# Schematico_Pompa.net
KiCad netlist of a schematic drawn in Altium Designer
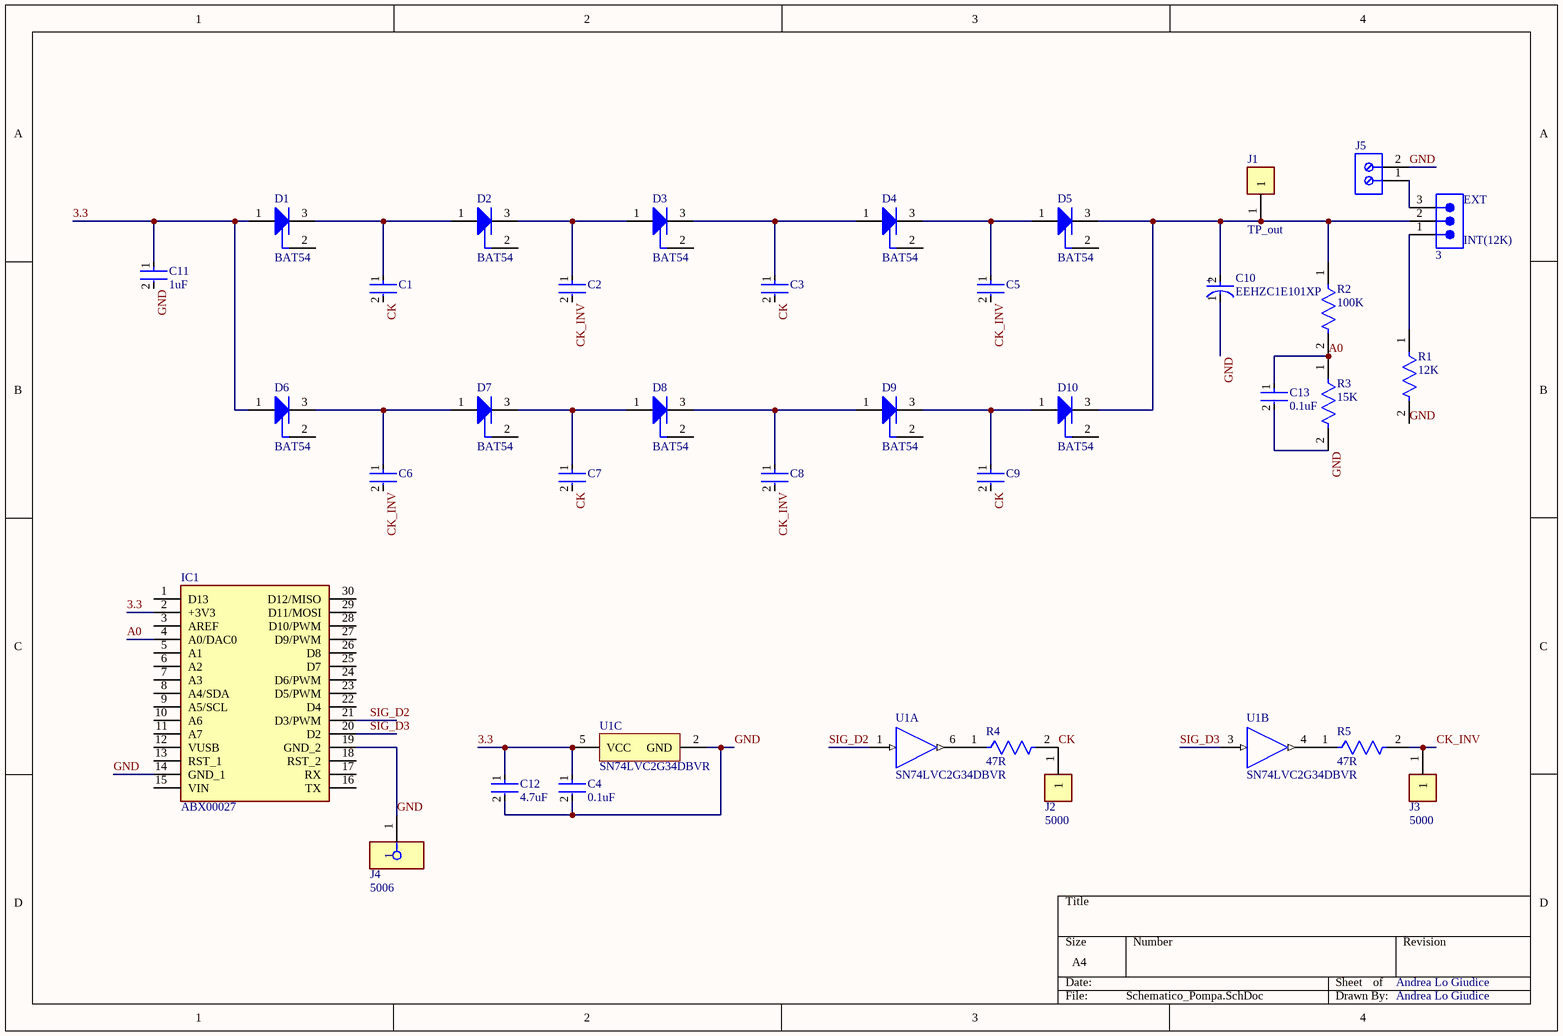
[diagram p0: Schematico_Pompa.SchDoc]

(export (version "E")
  (design (tool "Eeschema 10.0.6"))
  (components
    (comp (ref "3")
      (value "TSW-103-07-T-S")
      (footprint "SMTC-TSW-103-07-X-S")
      (description "0.025\" SQ Post Header, Through-hole, Vertical, -55 to 105 degC, 2.54 mm Pitch, 3-Pin, Male, RoHS")
      (fields (field (name "MANUFACTURER") "Samtec"))
      (libsource (lib "Altium Content Vault") (part "SMTC-TSW-103-X-X-S-X"))
    )
    (comp (ref "C1")
      (value "GRM188Z71E225ME43D")
      (footprint "FP-GRM188-0_2-IPC_C")
      (description "Chip Multilayer Ceramic Capacitors for General Purpose, 0603, 2.2uF, X7R, 15%, 20%, 25V")
      (libsource (lib "Altium Content Vault") (part "11868f565c42a9108669ba33697ecf6"))
    )
    (comp (ref "C2")
      (value "GRM188Z71E225ME43D")
      (footprint "FP-GRM188-0_2-IPC_C")
      (description "Chip Multilayer Ceramic Capacitors for General Purpose, 0603, 2.2uF, X7R, 15%, 20%, 25V")
      (libsource (lib "Altium Content Vault") (part "11868f565c42a9108669ba33697ecf6"))
    )
    (comp (ref "C3")
      (value "GRM188Z71E225ME43D")
      (footprint "FP-GRM188-0_2-IPC_C")
      (description "Chip Multilayer Ceramic Capacitors for General Purpose, 0603, 2.2uF, X7R, 15%, 20%, 25V")
      (libsource (lib "Altium Content Vault") (part "11868f565c42a9108669ba33697ecf6"))
    )
    (comp (ref "C4")
      (value "0.1uF")
      (footprint "FP-C0603C-CF-IPC_B")
      (description "CAP CER 0.1UF 16V X7R 0603")
      (fields (field (name "MANUFACTURER PART NUMBER") "C0603C104M4RACTU") (field (name "TOLERANCE") "0.2"))
      (libsource (lib "Altium Content Vault") (part "b4654b650e69147ec39a6b967a45e02"))
    )
    (comp (ref "C5")
      (value "GRM188Z71E225ME43D")
      (footprint "FP-GRM188-0_2-IPC_C")
      (description "Chip Multilayer Ceramic Capacitors for General Purpose, 0603, 2.2uF, X7R, 15%, 20%, 25V")
      (libsource (lib "Altium Content Vault") (part "11868f565c42a9108669ba33697ecf6"))
    )
    (comp (ref "C6")
      (value "GRM188Z71E225ME43D")
      (footprint "FP-GRM188-0_2-IPC_C")
      (description "Chip Multilayer Ceramic Capacitors for General Purpose, 0603, 2.2uF, X7R, 15%, 20%, 25V")
      (libsource (lib "Altium Content Vault") (part "11868f565c42a9108669ba33697ecf6"))
    )
    (comp (ref "C7")
      (value "GRM188Z71E225ME43D")
      (footprint "FP-GRM188-0_2-IPC_C")
      (description "Chip Multilayer Ceramic Capacitors for General Purpose, 0603, 2.2uF, X7R, 15%, 20%, 25V")
      (libsource (lib "Altium Content Vault") (part "11868f565c42a9108669ba33697ecf6"))
    )
    (comp (ref "C8")
      (value "GRM188Z71E225ME43D")
      (footprint "FP-GRM188-0_2-IPC_C")
      (description "Chip Multilayer Ceramic Capacitors for General Purpose, 0603, 2.2uF, X7R, 15%, 20%, 25V")
      (libsource (lib "Altium Content Vault") (part "11868f565c42a9108669ba33697ecf6"))
    )
    (comp (ref "C9")
      (value "GRM188Z71E225ME43D")
      (footprint "FP-GRM188-0_2-IPC_C")
      (description "Chip Multilayer Ceramic Capacitors for General Purpose, 0603, 2.2uF, X7R, 15%, 20%, 25V")
      (libsource (lib "Altium Content Vault") (part "11868f565c42a9108669ba33697ecf6"))
    )
    (comp (ref "C10")
      (value "EEHZC1E101XP")
      (footprint "FP-EEH-D8-MFG")
      (description "Conductive Polymer Hybrid Aluminum Electrolytic Capacitors 100uF ±20% 25V RADIAL SMT 6.3x7.7mm")
      (fields (field (name "TOLERANCE") "20%") (field (name "VOLTAGE") "25V"))
      (libsource (lib "Altium Content Vault") (part "a00bbbee19879c290e62620ae7e47b1"))
    )
    (comp (ref "C11")
      (value "1uF")
      (footprint "FP-CC0603-DA-IPC_B")
      (description "CC0603 1 uF X7R 10.00% 25 V")
      (fields
        (field (name "OCTOPART") "https://octopart.com/cc0603kpx7r8bb105-yageo-95714672")
        (field (name "MANUFACTURER PART NUMBER") "CC0603KPX7R8BB105")
      )
      (libsource (lib "Altium Content Vault") (part "11868f565c42a9108669ba33697ecf6"))
    )
    (comp (ref "C12")
      (value "4.7uF")
      (footprint "FP-CC0603-DA-IPC_B")
      (description "CAP CER 4.7UF 25V X5R 0603")
      (fields
        (field (name "OCTOPART") "https://octopart.com/cc0603mrx5r8bb475-yageo-81932637")
        (field (name "VOLTAGE") "25 V")
      )
      (libsource (lib "Altium Content Vault") (part "11868f565c42a9108669ba33697ecf6"))
    )
    (comp (ref "C13")
      (value "0.1uF")
      (footprint "FP-C0603C-CF-IPC_B")
      (description "CAP CER 0.1UF 16V X7R 0603")
      (fields (field (name "MANUFACTURER PART NUMBER") "C0603C104M4RACTU") (field (name "TOLERANCE") "0.2"))
      (libsource (lib "Altium Content Vault") (part "b4654b650e69147ec39a6b967a45e02"))
    )
    (comp (ref "D1")
      (value "BAT54")
      (footprint "INF-SOT23_L")
      (description "Silicon Schottky Diode, SOT23, Reel, Green")
      (fields (field (name "MANUFACTURER") "Infineon"))
      (libsource (lib "Altium Content Vault") (part "INF-D_A1K3-3"))
    )
    (comp (ref "D2")
      (value "BAT54")
      (footprint "INF-SOT23_L")
      (description "Silicon Schottky Diode, SOT23, Reel, Green")
      (fields (field (name "MANUFACTURER") "Infineon"))
      (libsource (lib "Altium Content Vault") (part "INF-D_A1K3-3"))
    )
    (comp (ref "D3")
      (value "BAT54")
      (footprint "INF-SOT23_L")
      (description "Silicon Schottky Diode, SOT23, Reel, Green")
      (fields (field (name "MANUFACTURER") "Infineon"))
      (libsource (lib "Altium Content Vault") (part "INF-D_A1K3-3"))
    )
    (comp (ref "D4")
      (value "BAT54")
      (footprint "INF-SOT23_L")
      (description "Silicon Schottky Diode, SOT23, Reel, Green")
      (fields (field (name "MANUFACTURER") "Infineon"))
      (libsource (lib "Altium Content Vault") (part "INF-D_A1K3-3"))
    )
    (comp (ref "D5")
      (value "BAT54")
      (footprint "INF-SOT23_L")
      (description "Silicon Schottky Diode, SOT23, Reel, Green")
      (fields (field (name "MANUFACTURER") "Infineon"))
      (libsource (lib "Altium Content Vault") (part "INF-D_A1K3-3"))
    )
    (comp (ref "D6")
      (value "BAT54")
      (footprint "INF-SOT23_L")
      (description "Silicon Schottky Diode, SOT23, Reel, Green")
      (fields (field (name "MANUFACTURER") "Infineon"))
      (libsource (lib "Altium Content Vault") (part "INF-D_A1K3-3"))
    )
    (comp (ref "D7")
      (value "BAT54")
      (footprint "INF-SOT23_L")
      (description "Silicon Schottky Diode, SOT23, Reel, Green")
      (fields (field (name "MANUFACTURER") "Infineon"))
      (libsource (lib "Altium Content Vault") (part "INF-D_A1K3-3"))
    )
    (comp (ref "D8")
      (value "BAT54")
      (footprint "INF-SOT23_L")
      (description "Silicon Schottky Diode, SOT23, Reel, Green")
      (fields (field (name "MANUFACTURER") "Infineon"))
      (libsource (lib "Altium Content Vault") (part "INF-D_A1K3-3"))
    )
    (comp (ref "D9")
      (value "BAT54")
      (footprint "INF-SOT23_L")
      (description "Silicon Schottky Diode, SOT23, Reel, Green")
      (fields (field (name "MANUFACTURER") "Infineon"))
      (libsource (lib "Altium Content Vault") (part "INF-D_A1K3-3"))
    )
    (comp (ref "D10")
      (value "BAT54")
      (footprint "INF-SOT23_L")
      (description "Silicon Schottky Diode, SOT23, Reel, Green")
      (fields (field (name "MANUFACTURER") "Infineon"))
      (libsource (lib "Altium Content Vault") (part "INF-D_A1K3-3"))
    )
    (comp (ref "IC1")
      (value "ABX00027")
      (footprint "SamacSys:ABX00027")
      (description "Development Boards & Kits - ARM Arduino Nano 33 IoT")
      (fields (field (name "MOUSER PART NUMBER") "782-ABX00027"))
      (libsource (lib "SamacSys") (part "ABX00027"))
    )
    (comp (ref "J1")
      (value "TP_out")
      (footprint "FP-5000-MFG")
      (description "PC TEST POINT MINIATURE RED")
      (libsource (lib "") (part "1e4615820a309e3ce90f9e6d957b7fa_1"))
    )
    (comp (ref "J2")
      (value "5000")
      (footprint "FP-5000-MFG")
      (description "PC TEST POINT MINIATURE RED")
      (libsource (lib "Altium Content Vault") (part "1e4615820a309e3ce90f9e6d957b7fa"))
    )
    (comp (ref "J3")
      (value "5000")
      (footprint "FP-5000-MFG")
      (description "PC TEST POINT MINIATURE RED")
      (libsource (lib "Altium Content Vault") (part "1e4615820a309e3ce90f9e6d957b7fa"))
    )
    (comp (ref "J4")
      (value "5006")
      (footprint "FP-5006-MFG")
      (description "PC TEST POINT COMPACT BLACK")
      (libsource (lib "Altium Content Vault") (part "98815daf2f2c152b0c43f5ab9800df6"))
    )
    (comp (ref "J5")
      (value "691214110002")
      (footprint "691214110002")
      (description "2141 Series 3.5MM Pitch Straight, Pcb Terminal Block, Through Hole, 2 Way")
      (fields (field (name "VOLTAGE") "300V"))
      (libsource (lib "morsetto_vite") (part "CMP-1502-02464-3"))
    )
    (comp (ref "R1")
      (value "12K")
      (footprint "FP-AT0603-IPC_C")
      (description "Thin Film Chip Resistors Automotive Grade 12kΩ 0.5% 50ppm/°C 0603")
      (fields (field (name "TOLERANCE") "0.5%"))
      (libsource (lib "Altium Content Vault") (part "1029c3af85768c4190bb7ad29bc67b5"))
    )
    (comp (ref "R2")
      (value "100K")
      (footprint "FP-CRGP0603-IPC_A")
      (description "CRGP 0603 100K 1%")
      (fields
        (field (name "MANUFACTURER") "TE")
        (field (name "OCTOPART") "https://octopart.com/crgp0603f100k-te+connectivity-91018719")
      )
      (libsource (lib "Altium Content Vault") (part "1029c3af85768c4190bb7ad29bc67b5"))
    )
    (comp (ref "R3")
      (value "15K")
      (footprint "FP-AC0603-IPC_C")
      (description "RES 15kΩ 1.00% 0.2W 0603")
      (libsource (lib "Altium Content Vault") (part "1029c3af85768c4190bb7ad29bc67b5"))
    )
    (comp (ref "R4")
      (value "47R")
      (footprint "FP-AC0603-IPC_C")
      (description "RES 47Ω 5.00% 0.1W 0603")
      (libsource (lib "Altium Content Vault") (part "1029c3af85768c4190bb7ad29bc67b5"))
    )
    (comp (ref "R5")
      (value "47R")
      (footprint "FP-AC0603-IPC_C")
      (description "RES 47Ω 5.00% 0.1W 0603")
      (libsource (lib "Altium Content Vault") (part "1029c3af85768c4190bb7ad29bc67b5"))
    )
    (comp (ref "U1")
      (value "SN74LVC2G34DBVR")
      (footprint "DBV0006A_N")
      (description "Dual Buffer Gate, DBV0006A, LARGE T&R")
      (fields
        (field (name "MANUFACTURER") "Texas Instruments")
        (field (name "GENERIC PART NUMBER") "SN74LVC2G34")
      )
      (libsource (lib "Altium Content Vault") (part "TI-SN74XXX2GXXX-6_A"))
    )
  )
  (nets
    (net (code "1") (name "/3.3") (class "Default")
      (node (ref "C11") (pin "1") (pinfunction "1_1") (pintype "passive"))
      (node (ref "C12") (pin "1") (pinfunction "1_1") (pintype "passive"))
      (node (ref "C4") (pin "1") (pinfunction "1_1") (pintype "passive"))
      (node (ref "D1") (pin "1") (pinfunction "A_1") (pintype "passive"))
      (node (ref "D6") (pin "1") (pinfunction "A_1") (pintype "passive"))
      (node (ref "IC1") (pin "2") (pinfunction "+3V3_2") (pintype "passive"))
      (node (ref "U1") (pin "5") (pinfunction "VCC_5") (pintype "power_in"))
    )
    (net (code "2") (name "/A0") (class "Default")
      (node (ref "C13") (pin "1") (pinfunction "1_1") (pintype "passive"))
      (node (ref "IC1") (pin "4") (pinfunction "A0/DAC0_4") (pintype "passive"))
      (node (ref "R2") (pin "2") (pinfunction "2_2") (pintype "passive"))
      (node (ref "R3") (pin "1") (pinfunction "1_1") (pintype "passive"))
    )
    (net (code "3") (name "/CK") (class "Default")
      (node (ref "C1") (pin "2") (pinfunction "2_2") (pintype "passive"))
      (node (ref "C3") (pin "2") (pinfunction "2_2") (pintype "passive"))
      (node (ref "C7") (pin "2") (pinfunction "2_2") (pintype "passive"))
      (node (ref "C9") (pin "2") (pinfunction "2_2") (pintype "passive"))
      (node (ref "J2") (pin "1") (pinfunction "1_1") (pintype "passive"))
      (node (ref "R4") (pin "2") (pinfunction "2_2") (pintype "passive"))
    )
    (net (code "4") (name "/CK_INV") (class "Default")
      (node (ref "C2") (pin "2") (pinfunction "2_2") (pintype "passive"))
      (node (ref "C5") (pin "2") (pinfunction "2_2") (pintype "passive"))
      (node (ref "C6") (pin "2") (pinfunction "2_2") (pintype "passive"))
      (node (ref "C8") (pin "2") (pinfunction "2_2") (pintype "passive"))
      (node (ref "J3") (pin "1") (pinfunction "1_1") (pintype "passive"))
      (node (ref "R5") (pin "2") (pinfunction "2_2") (pintype "passive"))
    )
    (net (code "5") (name "/GND") (class "Default")
      (node (ref "C10") (pin "1") (pinfunction "C_1") (pintype "passive"))
      (node (ref "C11") (pin "2") (pinfunction "2_2") (pintype "passive"))
      (node (ref "C12") (pin "2") (pinfunction "2_2") (pintype "passive"))
      (node (ref "C13") (pin "2") (pinfunction "2_2") (pintype "passive"))
      (node (ref "C4") (pin "2") (pinfunction "2_2") (pintype "passive"))
      (node (ref "IC1") (pin "14") (pinfunction "GND_1_14") (pintype "passive"))
      (node (ref "IC1") (pin "19") (pinfunction "GND_2_19") (pintype "passive"))
      (node (ref "J4") (pin "1") (pinfunction "1_1") (pintype "passive"))
      (node (ref "J5") (pin "2") (pinfunction "2_2") (pintype "passive"))
      (node (ref "R1") (pin "2") (pinfunction "2_2") (pintype "passive"))
      (node (ref "R3") (pin "2") (pinfunction "2_2") (pintype "passive"))
      (node (ref "U1") (pin "2") (pinfunction "GND_2") (pintype "power_in"))
    )
    (net (code "6") (name "/SIG_D2") (class "Default")
      (node (ref "IC1") (pin "21") (pinfunction "D3/PWM_21") (pintype "passive"))
      (node (ref "U1") (pin "1") (pinfunction "1A_1") (pintype "input"))
    )
    (net (code "7") (name "/SIG_D3") (class "Default")
      (node (ref "IC1") (pin "20") (pinfunction "D2_20") (pintype "passive"))
      (node (ref "U1") (pin "3") (pinfunction "2A_3") (pintype "input"))
    )
    (net (code "8") (name "Net-(3-Pad1)") (class "Default")
      (node (ref "3") (pin "1") (pinfunction "1_1") (pintype "passive"))
      (node (ref "R1") (pin "1") (pinfunction "1_1") (pintype "passive"))
    )
    (net (code "9") (name "Net-(3-Pad3)") (class "Default")
      (node (ref "3") (pin "3") (pinfunction "3_3") (pintype "passive"))
      (node (ref "J5") (pin "1") (pinfunction "1_1") (pintype "passive"))
    )
    (net (code "10") (name "Net-(C10-A)") (class "Default")
      (node (ref "3") (pin "2") (pinfunction "2_2") (pintype "passive"))
      (node (ref "C10") (pin "2") (pinfunction "A_2") (pintype "passive"))
      (node (ref "D10") (pin "3") (pinfunction "K_3") (pintype "passive"))
      (node (ref "D5") (pin "3") (pinfunction "K_3") (pintype "passive"))
      (node (ref "J1") (pin "1") (pinfunction "1_1") (pintype "passive"))
      (node (ref "R2") (pin "1") (pinfunction "1_1") (pintype "passive"))
    )
    (net (code "11") (name "Net-(D1-K)") (class "Default")
      (node (ref "C1") (pin "1") (pinfunction "1_1") (pintype "passive"))
      (node (ref "D1") (pin "3") (pinfunction "K_3") (pintype "passive"))
      (node (ref "D2") (pin "1") (pinfunction "A_1") (pintype "passive"))
    )
    (net (code "12") (name "Net-(D2-K)") (class "Default")
      (node (ref "C2") (pin "1") (pinfunction "1_1") (pintype "passive"))
      (node (ref "D2") (pin "3") (pinfunction "K_3") (pintype "passive"))
      (node (ref "D3") (pin "1") (pinfunction "A_1") (pintype "passive"))
    )
    (net (code "13") (name "Net-(D3-K)") (class "Default")
      (node (ref "C3") (pin "1") (pinfunction "1_1") (pintype "passive"))
      (node (ref "D3") (pin "3") (pinfunction "K_3") (pintype "passive"))
      (node (ref "D4") (pin "1") (pinfunction "A_1") (pintype "passive"))
    )
    (net (code "14") (name "Net-(D4-K)") (class "Default")
      (node (ref "C5") (pin "1") (pinfunction "1_1") (pintype "passive"))
      (node (ref "D4") (pin "3") (pinfunction "K_3") (pintype "passive"))
      (node (ref "D5") (pin "1") (pinfunction "A_1") (pintype "passive"))
    )
    (net (code "15") (name "Net-(D6-K)") (class "Default")
      (node (ref "C6") (pin "1") (pinfunction "1_1") (pintype "passive"))
      (node (ref "D6") (pin "3") (pinfunction "K_3") (pintype "passive"))
      (node (ref "D7") (pin "1") (pinfunction "A_1") (pintype "passive"))
    )
    (net (code "16") (name "Net-(D7-K)") (class "Default")
      (node (ref "C7") (pin "1") (pinfunction "1_1") (pintype "passive"))
      (node (ref "D7") (pin "3") (pinfunction "K_3") (pintype "passive"))
      (node (ref "D8") (pin "1") (pinfunction "A_1") (pintype "passive"))
    )
    (net (code "17") (name "Net-(D8-K)") (class "Default")
      (node (ref "C8") (pin "1") (pinfunction "1_1") (pintype "passive"))
      (node (ref "D8") (pin "3") (pinfunction "K_3") (pintype "passive"))
      (node (ref "D9") (pin "1") (pinfunction "A_1") (pintype "passive"))
    )
    (net (code "18") (name "Net-(D10-A)") (class "Default")
      (node (ref "C9") (pin "1") (pinfunction "1_1") (pintype "passive"))
      (node (ref "D10") (pin "1") (pinfunction "A_1") (pintype "passive"))
      (node (ref "D9") (pin "3") (pinfunction "K_3") (pintype "passive"))
    )
    (net (code "19") (name "Net-(U1A-1Y)") (class "Default")
      (node (ref "R4") (pin "1") (pinfunction "1_1") (pintype "passive"))
      (node (ref "U1") (pin "6") (pinfunction "1Y_6") (pintype "output"))
    )
    (net (code "20") (name "Net-(U1B-2Y)") (class "Default")
      (node (ref "R5") (pin "1") (pinfunction "1_1") (pintype "passive"))
      (node (ref "U1") (pin "4") (pinfunction "2Y_4") (pintype "output"))
    )
    (net (code "21") (name "unconnected-(D1-NC-Pad2)") (class "Default")
      (node (ref "D1") (pin "2") (pinfunction "NC_2") (pintype "passive"))
    )
    (net (code "22") (name "unconnected-(D2-NC-Pad2)") (class "Default")
      (node (ref "D2") (pin "2") (pinfunction "NC_2") (pintype "passive"))
    )
    (net (code "23") (name "unconnected-(D3-NC-Pad2)") (class "Default")
      (node (ref "D3") (pin "2") (pinfunction "NC_2") (pintype "passive"))
    )
    (net (code "24") (name "unconnected-(D4-NC-Pad2)") (class "Default")
      (node (ref "D4") (pin "2") (pinfunction "NC_2") (pintype "passive"))
    )
    (net (code "25") (name "unconnected-(D5-NC-Pad2)") (class "Default")
      (node (ref "D5") (pin "2") (pinfunction "NC_2") (pintype "passive"))
    )
    (net (code "26") (name "unconnected-(D6-NC-Pad2)") (class "Default")
      (node (ref "D6") (pin "2") (pinfunction "NC_2") (pintype "passive"))
    )
    (net (code "27") (name "unconnected-(D7-NC-Pad2)") (class "Default")
      (node (ref "D7") (pin "2") (pinfunction "NC_2") (pintype "passive"))
    )
    (net (code "28") (name "unconnected-(D8-NC-Pad2)") (class "Default")
      (node (ref "D8") (pin "2") (pinfunction "NC_2") (pintype "passive"))
    )
    (net (code "29") (name "unconnected-(D9-NC-Pad2)") (class "Default")
      (node (ref "D9") (pin "2") (pinfunction "NC_2") (pintype "passive"))
    )
    (net (code "30") (name "unconnected-(D10-NC-Pad2)") (class "Default")
      (node (ref "D10") (pin "2") (pinfunction "NC_2") (pintype "passive"))
    )
    (net (code "31") (name "unconnected-(IC1-A1-Pad5)") (class "Default")
      (node (ref "IC1") (pin "5") (pinfunction "A1_5") (pintype "passive"))
    )
    (net (code "32") (name "unconnected-(IC1-A2-Pad6)") (class "Default")
      (node (ref "IC1") (pin "6") (pinfunction "A2_6") (pintype "passive"))
    )
    (net (code "33") (name "unconnected-(IC1-A3-Pad7)") (class "Default")
      (node (ref "IC1") (pin "7") (pinfunction "A3_7") (pintype "passive"))
    )
    (net (code "34") (name "unconnected-(IC1-A4{slash}SDA-Pad8)") (class "Default")
      (node (ref "IC1") (pin "8") (pinfunction "A4/SDA_8") (pintype "passive"))
    )
    (net (code "35") (name "unconnected-(IC1-A5{slash}SCL-Pad9)") (class "Default")
      (node (ref "IC1") (pin "9") (pinfunction "A5/SCL_9") (pintype "passive"))
    )
    (net (code "36") (name "unconnected-(IC1-A6-Pad10)") (class "Default")
      (node (ref "IC1") (pin "10") (pinfunction "A6_10") (pintype "passive"))
    )
    (net (code "37") (name "unconnected-(IC1-A7-Pad11)") (class "Default")
      (node (ref "IC1") (pin "11") (pinfunction "A7_11") (pintype "passive"))
    )
    (net (code "38") (name "unconnected-(IC1-AREF-Pad3)") (class "Default")
      (node (ref "IC1") (pin "3") (pinfunction "AREF_3") (pintype "passive"))
    )
    (net (code "39") (name "unconnected-(IC1-D4-Pad22)") (class "Default")
      (node (ref "IC1") (pin "22") (pinfunction "D4_22") (pintype "passive"))
    )
    (net (code "40") (name "unconnected-(IC1-D5{slash}PWM-Pad23)") (class "Default")
      (node (ref "IC1") (pin "23") (pinfunction "D5/PWM_23") (pintype "passive"))
    )
    (net (code "41") (name "unconnected-(IC1-D6{slash}PWM-Pad24)") (class "Default")
      (node (ref "IC1") (pin "24") (pinfunction "D6/PWM_24") (pintype "passive"))
    )
    (net (code "42") (name "unconnected-(IC1-D7-Pad25)") (class "Default")
      (node (ref "IC1") (pin "25") (pinfunction "D7_25") (pintype "passive"))
    )
    (net (code "43") (name "unconnected-(IC1-D8-Pad26)") (class "Default")
      (node (ref "IC1") (pin "26") (pinfunction "D8_26") (pintype "passive"))
    )
    (net (code "44") (name "unconnected-(IC1-D9{slash}PWM-Pad27)") (class "Default")
      (node (ref "IC1") (pin "27") (pinfunction "D9/PWM_27") (pintype "passive"))
    )
    (net (code "45") (name "unconnected-(IC1-D10{slash}PWM-Pad28)") (class "Default")
      (node (ref "IC1") (pin "28") (pinfunction "D10/PWM_28") (pintype "passive"))
    )
    (net (code "46") (name "unconnected-(IC1-D11{slash}MOSI-Pad29)") (class "Default")
      (node (ref "IC1") (pin "29") (pinfunction "D11/MOSI_29") (pintype "passive"))
    )
    (net (code "47") (name "unconnected-(IC1-D12{slash}MISO-Pad30)") (class "Default")
      (node (ref "IC1") (pin "30") (pinfunction "D12/MISO_30") (pintype "passive"))
    )
    (net (code "48") (name "unconnected-(IC1-D13-Pad1)") (class "Default")
      (node (ref "IC1") (pin "1") (pinfunction "D13_1") (pintype "passive"))
    )
    (net (code "49") (name "unconnected-(IC1-RST_1-Pad13)") (class "Default")
      (node (ref "IC1") (pin "13") (pinfunction "RST_1_13") (pintype "passive"))
    )
    (net (code "50") (name "unconnected-(IC1-RST_2-Pad18)") (class "Default")
      (node (ref "IC1") (pin "18") (pinfunction "RST_2_18") (pintype "passive"))
    )
    (net (code "51") (name "unconnected-(IC1-RX-Pad17)") (class "Default")
      (node (ref "IC1") (pin "17") (pinfunction "RX_17") (pintype "passive"))
    )
    (net (code "52") (name "unconnected-(IC1-TX-Pad16)") (class "Default")
      (node (ref "IC1") (pin "16") (pinfunction "TX_16") (pintype "passive"))
    )
    (net (code "53") (name "unconnected-(IC1-VIN-Pad15)") (class "Default")
      (node (ref "IC1") (pin "15") (pinfunction "VIN_15") (pintype "passive"))
    )
    (net (code "54") (name "unconnected-(IC1-VUSB-Pad12)") (class "Default")
      (node (ref "IC1") (pin "12") (pinfunction "VUSB_12") (pintype "passive"))
    )
  )
)
